# ETZ_TWICE.net
KiCad netlist of a schematic drawn in Altium Designer
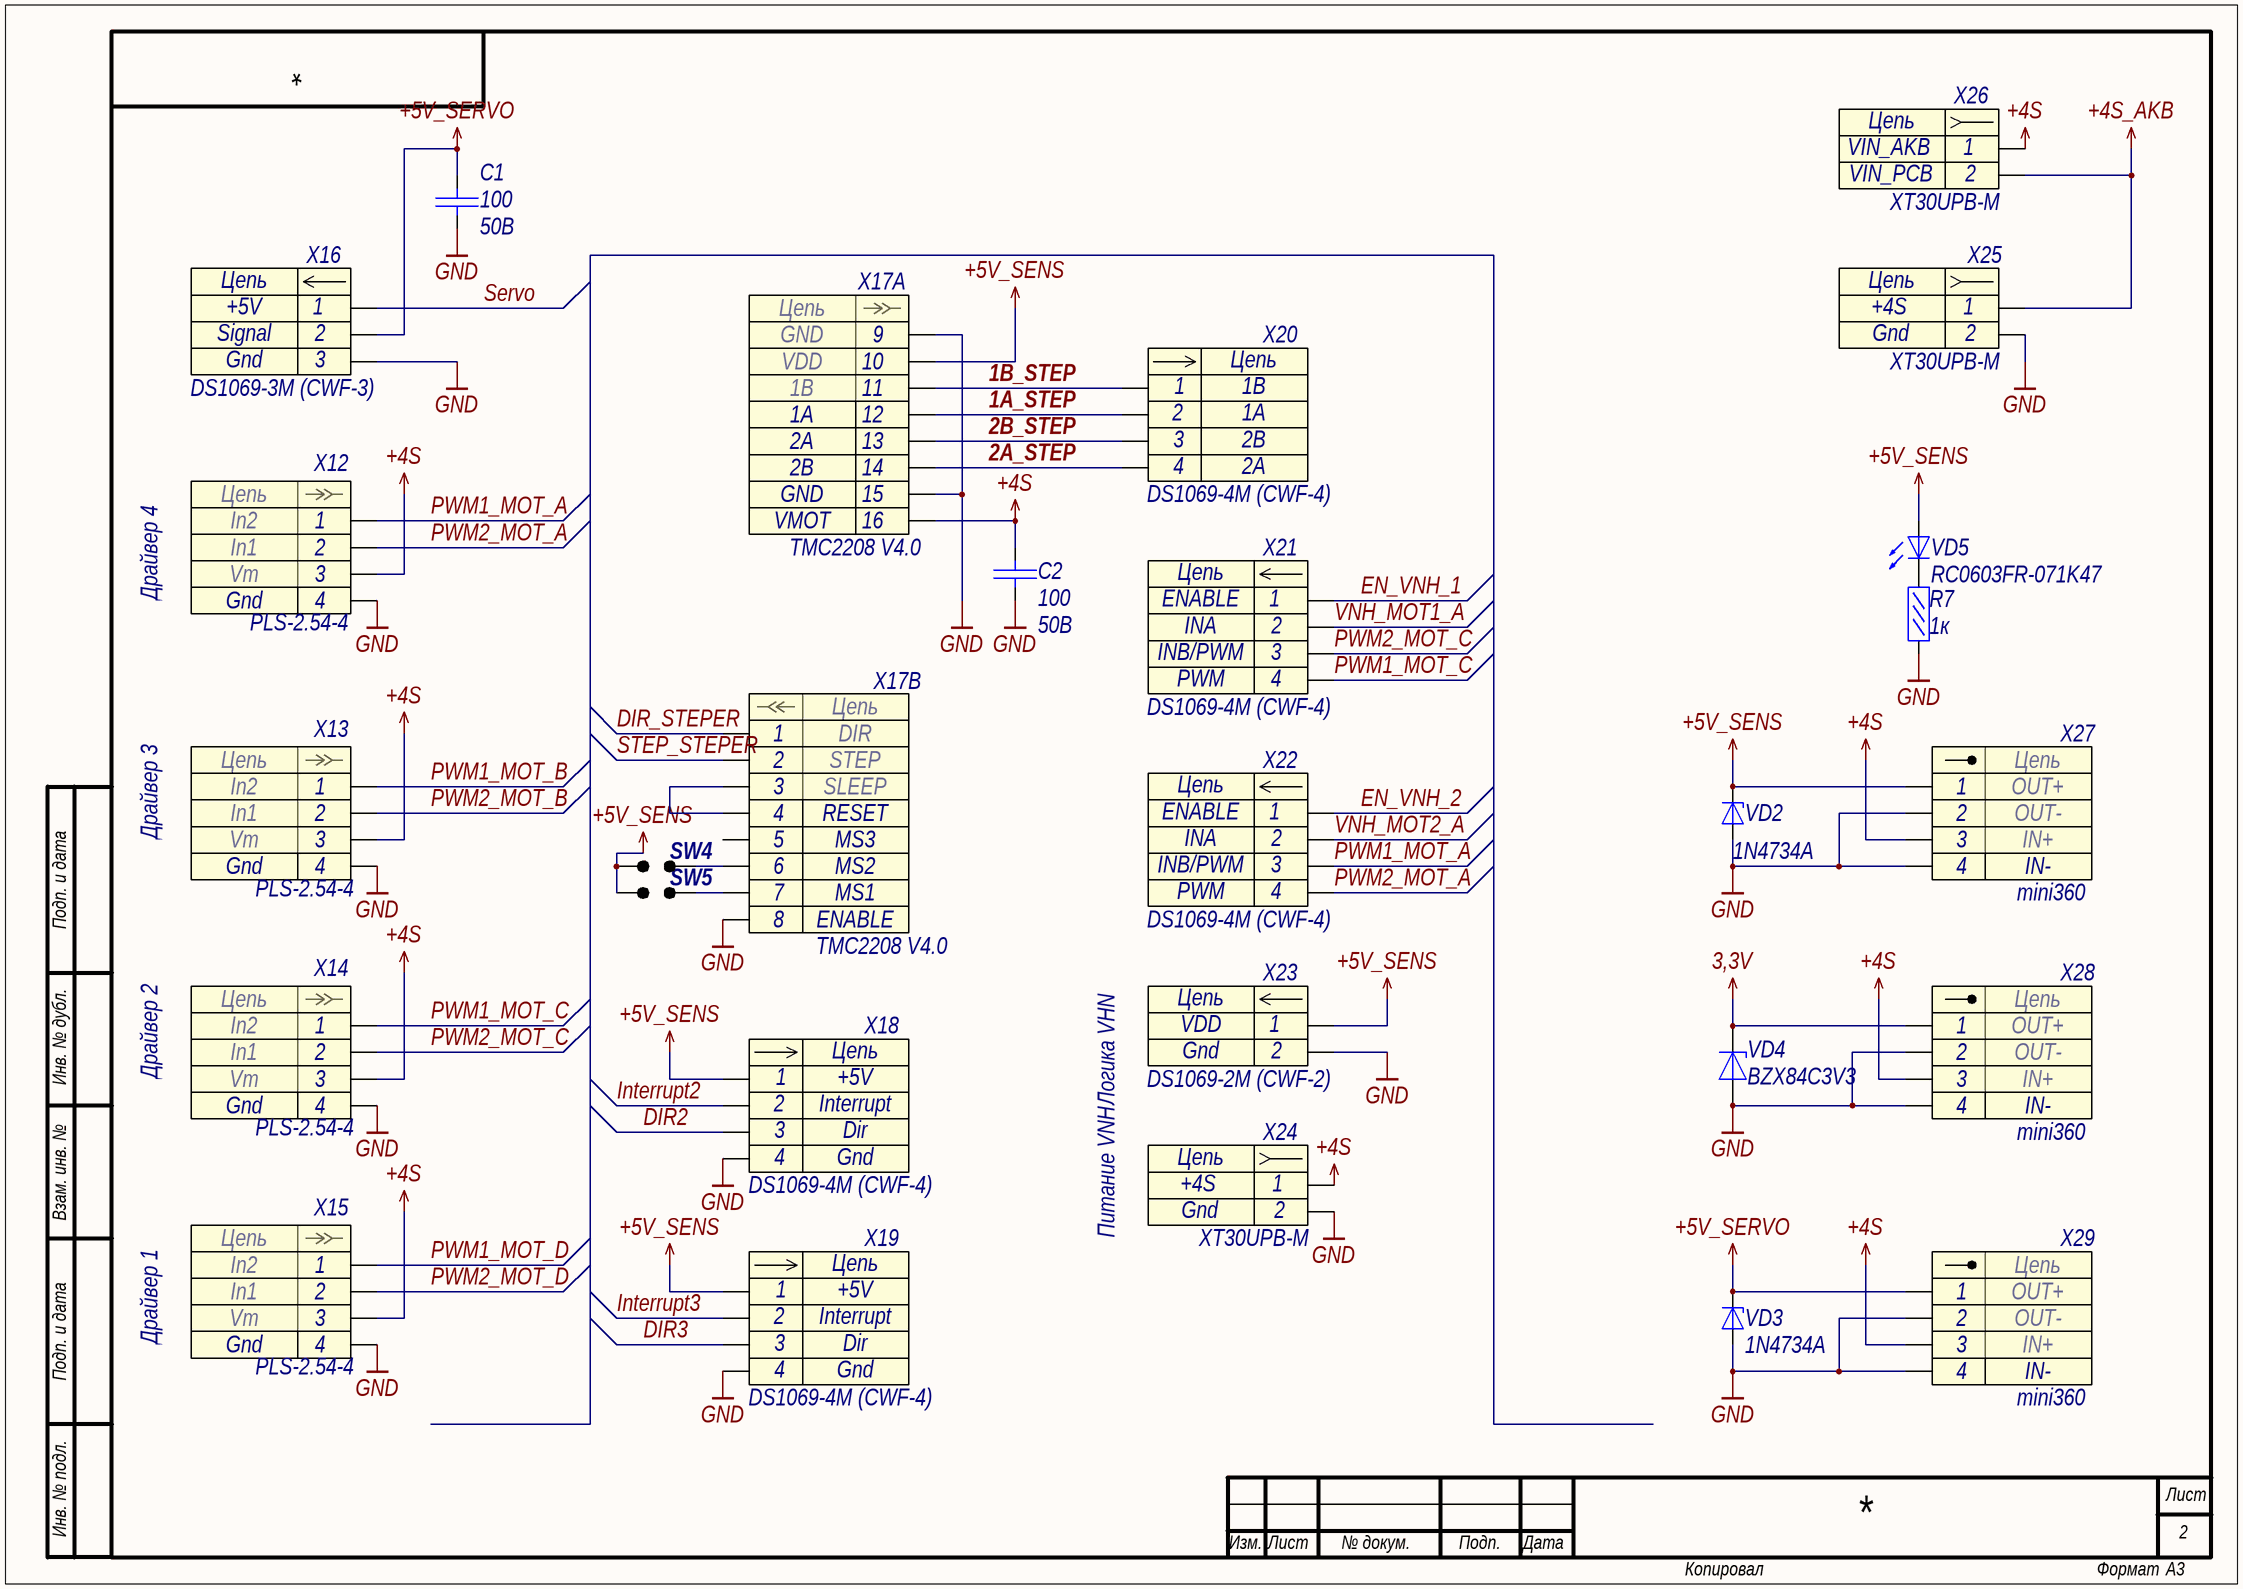
[diagram p0: ETZ_TWICE.SchDoc]

(export (version "E")
  (design (tool "Eeschema 10.0.6"))
  (components
    (comp (ref "C1")
      (value "100")
      (footprint "C0603")
      (description "Конденсатор кер. 100пФ 50В")
      (fields (field (name "MANUFACTURER") "Yageo") (field (name "VOLTAGE") "50В"))
      (libsource (lib "capacitors") (part "CC0603JRNPO9BN101"))
    )
    (comp (ref "C2")
      (value "100")
      (footprint "C0603")
      (description "Конденсатор кер. 100пФ 50В")
      (fields (field (name "MANUFACTURER") "Yageo") (field (name "VOLTAGE") "50В"))
      (libsource (lib "capacitors") (part "CC0603JRNPO9BN101"))
    )
    (comp (ref "R7")
      (value "1к")
      (footprint "R0603")
      (description "Резистор 1кОм 0,063Вт 1%")
      (fields (field (name "MANUFACTURER") "YAGEO") (field (name "TOLERANCE") "1%"))
      (libsource (lib "resistors") (part "RC0603FR-071KL"))
    )
    (comp (ref "SW4")
      (value "~")
      (footprint "Jumper_0.5x1")
      (description "Перемычка")
      (libsource (lib "MZBT_SchLibrary") (part "Jumper"))
    )
    (comp (ref "SW5")
      (value "~")
      (footprint "Jumper_0.5x1")
      (description "Перемычка")
      (libsource (lib "MZBT_SchLibrary") (part "Jumper"))
    )
    (comp (ref "VD2")
      (value "1N4734A")
      (footprint "DO-41")
      (description "Стабилитрон 5.6В, 5%, 1Вт, 1N4734A")
      (libsource (lib "diodes") (part "1N4734A"))
    )
    (comp (ref "VD3")
      (value "1N4734A")
      (footprint "DO-41")
      (description "Стабилитрон 5.6В, 5%, 1Вт, 1N4734A")
      (libsource (lib "diodes") (part "1N4734A"))
    )
    (comp (ref "VD4")
      (value "BZX84C3V3")
      (footprint "SOT23-3")
      (description "Стабилитрон 3,3В")
      (libsource (lib "diodes") (part "BZX84C3V3"))
    )
    (comp (ref "VD5")
      (value "RC0603FR-071K47")
      (footprint "VD0603")
      (description "Светодтод зеленый SMD Foryard Optoelectronics Co.")
      (libsource (lib "diodes") (part "FYLS-0603BUGC"))
    )
    (comp (ref "X12")
      (value "PLS-2.54-4")
      (footprint "DRV8871")
      (fields (field (name "NAM") "PLS-2.54-4"))
      (libsource (lib "LibraryPloshchadnaia") (part "PLS-2.54-4"))
    )
    (comp (ref "X13")
      (value "PLS-2.54-4")
      (footprint "DRV8871")
      (fields (field (name "NAM") "PLS-2.54-4"))
      (libsource (lib "LibraryPloshchadnaia") (part "PLS-2.54-4"))
    )
    (comp (ref "X14")
      (value "PLS-2.54-4")
      (footprint "DRV8871")
      (fields (field (name "NAM") "PLS-2.54-4"))
      (libsource (lib "LibraryPloshchadnaia") (part "PLS-2.54-4"))
    )
    (comp (ref "X15")
      (value "PLS-2.54-4")
      (footprint "DRV8871")
      (fields (field (name "NAM") "PLS-2.54-4"))
      (libsource (lib "LibraryPloshchadnaia") (part "PLS-2.54-4"))
    )
    (comp (ref "X16")
      (value "DS1069-3M (CWF-3)")
      (footprint "CWF-3")
      (description "Разъем - 3 конт. прямая вилка на плату")
      (libsource (lib "headers") (part "CWF-3"))
    )
    (comp (ref "X17") (value "TMC2208 V4.0") (footprint "A4988") (libsource (lib "") (part "A4988_1")))
    (comp (ref "X18")
      (value "DS1069-4M (CWF-4)")
      (footprint "CWF-4")
      (description "Разъем - 4 конт. прямая вилка на плату")
      (fields (field (name "NAME") "DS1069-4M (CWF-4)"))
      (libsource (lib "") (part "CWF-4_1"))
    )
    (comp (ref "X19")
      (value "DS1069-4M (CWF-4)")
      (footprint "CWF-4")
      (description "Разъем - 4 конт. прямая вилка на плату")
      (fields (field (name "NAME") "DS1069-4M (CWF-4)"))
      (libsource (lib "") (part "CWF-4_1"))
    )
    (comp (ref "X20")
      (value "DS1069-4M (CWF-4)")
      (footprint "CWF-4")
      (description "Разъем - 4 конт. прямая вилка на плату")
      (fields (field (name "NAME") "DS1069-4M (CWF-4)"))
      (libsource (lib "") (part "CWF-4_1"))
    )
    (comp (ref "X21")
      (value "DS1069-4M (CWF-4)")
      (footprint "CWF-4")
      (description "Разъем - 4 конт. прямая вилка на плату")
      (libsource (lib "headers") (part "CWF-4"))
    )
    (comp (ref "X22")
      (value "DS1069-4M (CWF-4)")
      (footprint "CWF-4")
      (description "Разъем - 4 конт. прямая вилка на плату")
      (libsource (lib "headers") (part "CWF-4"))
    )
    (comp (ref "X23")
      (value "DS1069-2M (CWF-2)")
      (footprint "CWF-2")
      (description "Разъем - 2 конт. прямая вилка на плату")
      (libsource (lib "headers") (part "CWF-2"))
    )
    (comp (ref "X24")
      (value "XT30UPB-M")
      (footprint "XT30UPB-M")
      (libsource (lib "MZBT_SchLibrary") (part "XT30UPB-M"))
    )
    (comp (ref "X25")
      (value "XT30UPB-M")
      (footprint "XT30UPB-M")
      (libsource (lib "MZBT_SchLibrary") (part "XT30UPB-M"))
    )
    (comp (ref "X26")
      (value "XT30UPB-M")
      (footprint "XT30UPB-M")
      (libsource (lib "MZBT_SchLibrary") (part "XT30UPB-M"))
    )
    (comp (ref "X27")
      (value "mini360")
      (footprint "mini360")
      (description "стаб 18 на 12 мм")
      (libsource (lib "LibraryPloshchadnaia") (part "mini360"))
    )
    (comp (ref "X28")
      (value "mini360")
      (footprint "mini360")
      (description "стаб 18 на 12 мм")
      (libsource (lib "LibraryPloshchadnaia") (part "mini360"))
    )
    (comp (ref "X29")
      (value "mini360")
      (footprint "mini360")
      (description "стаб 18 на 12 мм")
      (libsource (lib "LibraryPloshchadnaia") (part "mini360"))
    )
  )
  (nets
    (net (code "1") (name "+4S") (class "Default")
      (node (ref "C2") (pin "1") (pinfunction "1_1") (pintype "passive"))
      (node (ref "X12") (pin "3") (pinfunction "3_3") (pintype "passive"))
      (node (ref "X13") (pin "3") (pinfunction "3_3") (pintype "passive"))
      (node (ref "X14") (pin "3") (pinfunction "3_3") (pintype "passive"))
      (node (ref "X15") (pin "3") (pinfunction "3_3") (pintype "passive"))
      (node (ref "X17") (pin "16") (pinfunction "16_16") (pintype "passive"))
      (node (ref "X24") (pin "1") (pinfunction "1_1") (pintype "passive"))
      (node (ref "X26") (pin "1") (pinfunction "1_1") (pintype "passive"))
      (node (ref "X27") (pin "3") (pinfunction "3_3") (pintype "passive"))
      (node (ref "X28") (pin "3") (pinfunction "3_3") (pintype "passive"))
      (node (ref "X29") (pin "3") (pinfunction "3_3") (pintype "passive"))
    )
    (net (code "2") (name "+4S_AKB") (class "Default")
      (node (ref "X25") (pin "1") (pinfunction "1_1") (pintype "passive"))
      (node (ref "X26") (pin "2") (pinfunction "2_2") (pintype "passive"))
    )
    (net (code "3") (name "+5V_SENS") (class "Default")
      (node (ref "SW4") (pin "1") (pinfunction "1_1") (pintype "passive"))
      (node (ref "SW5") (pin "1") (pinfunction "1_1") (pintype "passive"))
      (node (ref "VD2") (pin "2") (pinfunction "K_2") (pintype "passive"))
      (node (ref "VD5") (pin "1") (pinfunction "A_1") (pintype "passive"))
      (node (ref "X17") (pin "10") (pinfunction "10_10") (pintype "passive"))
      (node (ref "X18") (pin "1") (pinfunction "1_1") (pintype "passive"))
      (node (ref "X19") (pin "1") (pinfunction "1_1") (pintype "passive"))
      (node (ref "X23") (pin "1") (pinfunction "1_1") (pintype "passive"))
      (node (ref "X27") (pin "1") (pinfunction "1_1") (pintype "passive"))
    )
    (net (code "4") (name "+5V_SERVO") (class "Default")
      (node (ref "C1") (pin "1") (pinfunction "1_1") (pintype "passive"))
      (node (ref "VD3") (pin "2") (pinfunction "K_2") (pintype "passive"))
      (node (ref "X16") (pin "2") (pinfunction "2_2") (pintype "passive"))
      (node (ref "X29") (pin "1") (pinfunction "1_1") (pintype "passive"))
    )
    (net (code "5") (name "/1A_STEP") (class "Default")
      (node (ref "X17") (pin "12") (pinfunction "12_12") (pintype "passive"))
      (node (ref "X20") (pin "2") (pinfunction "2_2") (pintype "passive"))
    )
    (net (code "6") (name "/1B_STEP") (class "Default")
      (node (ref "X17") (pin "11") (pinfunction "11_11") (pintype "passive"))
      (node (ref "X20") (pin "1") (pinfunction "1_1") (pintype "passive"))
    )
    (net (code "7") (name "/2A_STEP") (class "Default")
      (node (ref "X17") (pin "14") (pinfunction "14_14") (pintype "passive"))
      (node (ref "X20") (pin "4") (pinfunction "4_4") (pintype "passive"))
    )
    (net (code "8") (name "/2B_STEP") (class "Default")
      (node (ref "X17") (pin "13") (pinfunction "13_13") (pintype "passive"))
      (node (ref "X20") (pin "3") (pinfunction "3_3") (pintype "passive"))
    )
    (net (code "9") (name "/DIR2") (class "Default")
      (node (ref "X18") (pin "3") (pinfunction "3_3") (pintype "passive"))
    )
    (net (code "10") (name "/DIR3") (class "Default")
      (node (ref "X19") (pin "3") (pinfunction "3_3") (pintype "passive"))
    )
    (net (code "11") (name "/DIR_STEPER") (class "Default")
      (node (ref "X17") (pin "1") (pinfunction "1_1") (pintype "passive"))
    )
    (net (code "12") (name "/EN_VNH_1") (class "Default")
      (node (ref "X21") (pin "1") (pinfunction "1_1") (pintype "passive"))
    )
    (net (code "13") (name "/EN_VNH_2") (class "Default")
      (node (ref "X22") (pin "1") (pinfunction "1_1") (pintype "passive"))
    )
    (net (code "14") (name "/Interrupt2") (class "Default")
      (node (ref "X18") (pin "2") (pinfunction "2_2") (pintype "passive"))
    )
    (net (code "15") (name "/Interrupt3") (class "Default")
      (node (ref "X19") (pin "2") (pinfunction "2_2") (pintype "passive"))
    )
    (net (code "16") (name "/PWM1_MOT_A") (class "Default")
      (node (ref "X12") (pin "1") (pinfunction "1_1") (pintype "passive"))
      (node (ref "X22") (pin "3") (pinfunction "3_3") (pintype "passive"))
    )
    (net (code "17") (name "/PWM1_MOT_B") (class "Default")
      (node (ref "X13") (pin "1") (pinfunction "1_1") (pintype "passive"))
    )
    (net (code "18") (name "/PWM1_MOT_C") (class "Default")
      (node (ref "X14") (pin "1") (pinfunction "1_1") (pintype "passive"))
      (node (ref "X21") (pin "4") (pinfunction "4_4") (pintype "passive"))
    )
    (net (code "19") (name "/PWM1_MOT_D") (class "Default")
      (node (ref "X15") (pin "1") (pinfunction "1_1") (pintype "passive"))
    )
    (net (code "20") (name "/PWM2_MOT_A") (class "Default")
      (node (ref "X12") (pin "2") (pinfunction "2_2") (pintype "passive"))
      (node (ref "X22") (pin "4") (pinfunction "4_4") (pintype "passive"))
    )
    (net (code "21") (name "/PWM2_MOT_B") (class "Default")
      (node (ref "X13") (pin "2") (pinfunction "2_2") (pintype "passive"))
    )
    (net (code "22") (name "/PWM2_MOT_C") (class "Default")
      (node (ref "X14") (pin "2") (pinfunction "2_2") (pintype "passive"))
      (node (ref "X21") (pin "3") (pinfunction "3_3") (pintype "passive"))
    )
    (net (code "23") (name "/PWM2_MOT_D") (class "Default")
      (node (ref "X15") (pin "2") (pinfunction "2_2") (pintype "passive"))
    )
    (net (code "24") (name "/STEP_STEPER") (class "Default")
      (node (ref "X17") (pin "2") (pinfunction "2_2") (pintype "passive"))
    )
    (net (code "25") (name "/Servo") (class "Default")
      (node (ref "X16") (pin "1") (pinfunction "1_1") (pintype "passive"))
    )
    (net (code "26") (name "/VNH_MOT1_A") (class "Default")
      (node (ref "X21") (pin "2") (pinfunction "2_2") (pintype "passive"))
    )
    (net (code "27") (name "/VNH_MOT2_A") (class "Default")
      (node (ref "X22") (pin "2") (pinfunction "2_2") (pintype "passive"))
    )
    (net (code "28") (name "3,3V") (class "Default")
      (node (ref "VD4") (pin "3") (pinfunction "K_3") (pintype "passive"))
      (node (ref "X28") (pin "1") (pinfunction "1_1") (pintype "passive"))
    )
    (net (code "29") (name "GND") (class "Default")
      (node (ref "C1") (pin "2") (pinfunction "2_2") (pintype "passive"))
      (node (ref "C2") (pin "2") (pinfunction "2_2") (pintype "passive"))
      (node (ref "R7") (pin "1") (pinfunction "1_1") (pintype "passive"))
      (node (ref "VD2") (pin "1") (pinfunction "A_1") (pintype "passive"))
      (node (ref "VD3") (pin "1") (pinfunction "A_1") (pintype "passive"))
      (node (ref "VD4") (pin "1") (pinfunction "A_1") (pintype "passive"))
      (node (ref "X12") (pin "4") (pinfunction "4_4") (pintype "passive"))
      (node (ref "X13") (pin "4") (pinfunction "4_4") (pintype "passive"))
      (node (ref "X14") (pin "4") (pinfunction "4_4") (pintype "passive"))
      (node (ref "X15") (pin "4") (pinfunction "4_4") (pintype "passive"))
      (node (ref "X16") (pin "3") (pinfunction "3_3") (pintype "passive"))
      (node (ref "X17") (pin "15") (pinfunction "15_15") (pintype "passive"))
      (node (ref "X17") (pin "8") (pinfunction "8_8") (pintype "passive"))
      (node (ref "X17") (pin "9") (pinfunction "9_9") (pintype "passive"))
      (node (ref "X18") (pin "4") (pinfunction "4_4") (pintype "passive"))
      (node (ref "X19") (pin "4") (pinfunction "4_4") (pintype "passive"))
      (node (ref "X23") (pin "2") (pinfunction "2_2") (pintype "passive"))
      (node (ref "X24") (pin "2") (pinfunction "2_2") (pintype "passive"))
      (node (ref "X25") (pin "2") (pinfunction "2_2") (pintype "passive"))
      (node (ref "X27") (pin "2") (pinfunction "2_2") (pintype "passive"))
      (node (ref "X27") (pin "4") (pinfunction "4_4") (pintype "passive"))
      (node (ref "X28") (pin "2") (pinfunction "2_2") (pintype "passive"))
      (node (ref "X28") (pin "4") (pinfunction "4_4") (pintype "passive"))
      (node (ref "X29") (pin "2") (pinfunction "2_2") (pintype "passive"))
      (node (ref "X29") (pin "4") (pinfunction "4_4") (pintype "passive"))
    )
    (net (code "30") (name "Net-(SW4-Pad2)") (class "Default")
      (node (ref "SW4") (pin "2") (pinfunction "2_2") (pintype "passive"))
      (node (ref "X17") (pin "6") (pinfunction "6_6") (pintype "passive"))
    )
    (net (code "31") (name "Net-(SW5-Pad2)") (class "Default")
      (node (ref "SW5") (pin "2") (pinfunction "2_2") (pintype "passive"))
      (node (ref "X17") (pin "7") (pinfunction "7_7") (pintype "passive"))
    )
    (net (code "32") (name "Net-(VD5-K)") (class "Default")
      (node (ref "R7") (pin "2") (pinfunction "2_2") (pintype "passive"))
      (node (ref "VD5") (pin "2") (pinfunction "K_2") (pintype "passive"))
    )
    (net (code "33") (name "Net-(X17-Pad3)") (class "Default")
      (node (ref "X17") (pin "3") (pinfunction "3_3") (pintype "passive"))
      (node (ref "X17") (pin "4") (pinfunction "4_4") (pintype "passive"))
    )
    (net (code "34") (name "unconnected-(X17-Pad5)") (class "Default")
      (node (ref "X17") (pin "5") (pinfunction "5_5") (pintype "passive"))
    )
    (net (code "35") (name "unconnected-(X27-Pad0)") (class "Default")
      (node (ref "X27") (pin "0") (pinfunction "0_0") (pintype "passive"))
    )
    (net (code "36") (name "unconnected-(X28-Pad0)") (class "Default")
      (node (ref "X28") (pin "0") (pinfunction "0_0") (pintype "passive"))
    )
    (net (code "37") (name "unconnected-(X29-Pad0)") (class "Default")
      (node (ref "X29") (pin "0") (pinfunction "0_0") (pintype "passive"))
    )
  )
)
